# Enclosure_100x68_BHWL3.net
KiCad netlist of a schematic drawn in EAGLE
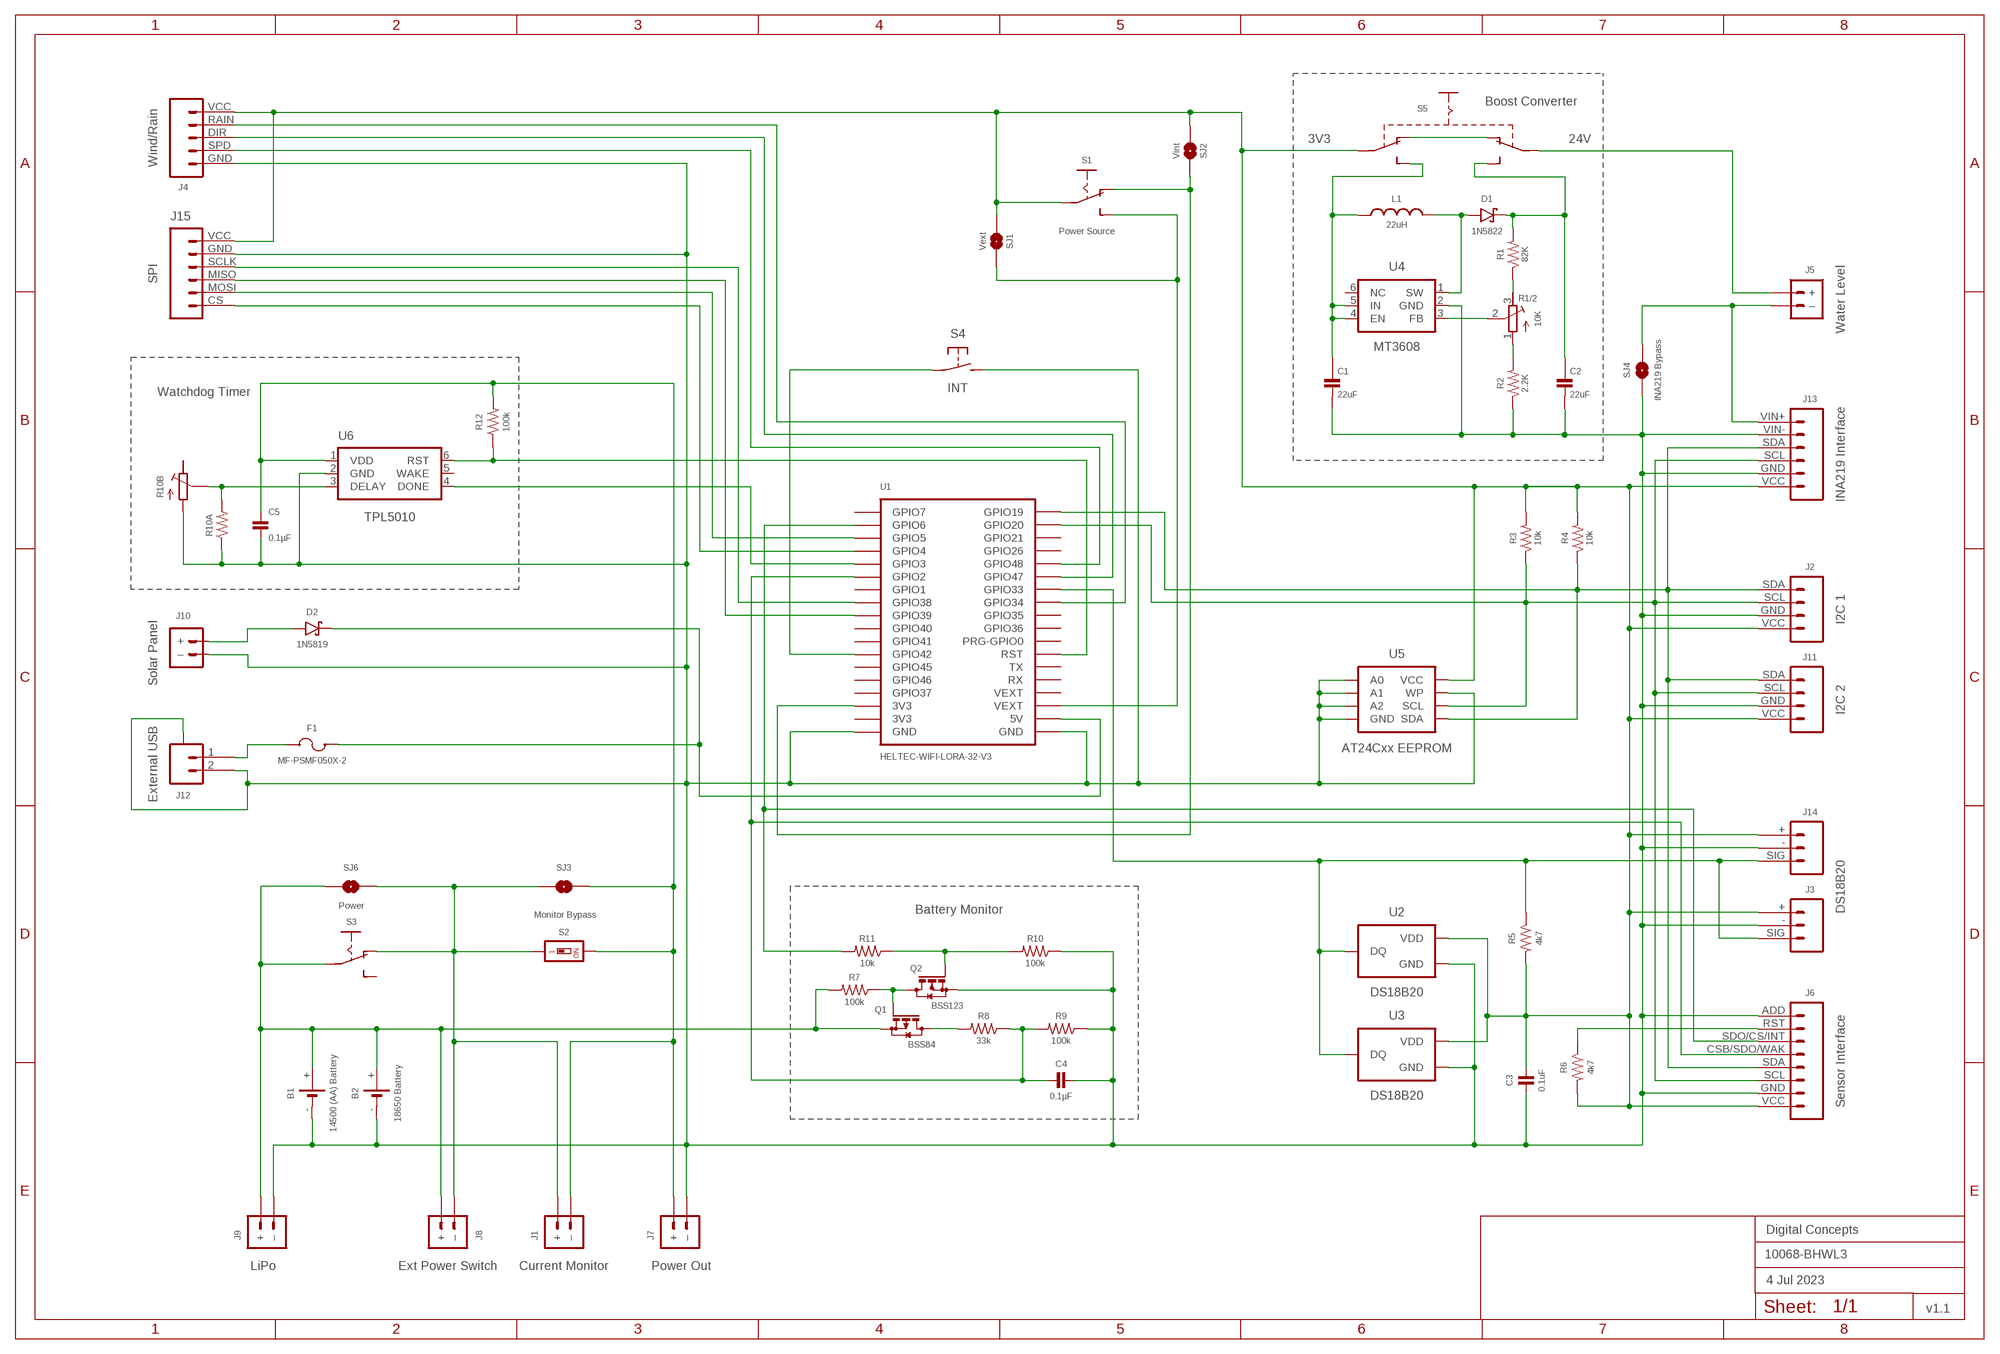
[diagram p0: schematic, sheet 1]

(export (version "E")
  (design (tool "Eeschema 10.0.6"))
  (components
    (comp (ref "B1")
      (value "14500 (AA) Battery")
      (footprint "eagle-import:BATTERY-14500")
      (libsource (lib "eagle-import") (part "BATTERY-HOLDER-14500(AA)"))
    )
    (comp (ref "B2")
      (value "18650 Battery")
      (footprint "eagle-import:BATTERY-18650")
      (libsource (lib "eagle-import") (part "BATTERY-HOLDER-18650"))
    )
    (comp (ref "C1")
      (value "22uF")
      (footprint "eagle-import:C1206")
      (libsource (lib "eagle-import") (part "CAPACITOR-1206"))
    )
    (comp (ref "C2")
      (value "22uF")
      (footprint "eagle-import:C1206")
      (libsource (lib "eagle-import") (part "CAPACITOR-1206"))
    )
    (comp (ref "C3")
      (value "0.1uF")
      (footprint "eagle-import:C0805")
      (libsource (lib "eagle-import") (part "CAPACITOR-0805"))
    )
    (comp (ref "C4")
      (value "0.1µF")
      (footprint "eagle-import:C0805")
      (libsource (lib "eagle-import") (part "CAPACITOR-0805"))
    )
    (comp (ref "C5")
      (value "0.1µF")
      (footprint "eagle-import:C0805")
      (libsource (lib "eagle-import") (part "CAPACITOR-0805"))
    )
    (comp (ref "D1")
      (value "1N5822")
      (footprint "eagle-import:DIODE_SMB")
      (libsource (lib "eagle-import") (part "DIODE-SCHOTTKY-1N5822"))
    )
    (comp (ref "D2")
      (value "1N5819")
      (footprint "eagle-import:SOD-123")
      (libsource (lib "eagle-import") (part "1N5819-SOD-123"))
    )
    (comp (ref "F1")
      (value "MF-PSMF050X-2")
      (footprint "eagle-import:F0805")
      (libsource (lib "eagle-import") (part "MF-PSMF050X-2"))
    )
    (comp (ref "J1")
      (value "Current Monitor")
      (footprint "eagle-import:JST-PH2.0-2-HORIZONTAL")
      (libsource (lib "eagle-import") (part "JST-PH2.0-2-HORIZONTALJST-PTH-2"))
    )
    (comp (ref "J2")
      (value "I2C 1")
      (footprint "eagle-import:JST-PH2.0-4-VERTICAL-I2C")
      (libsource (lib "eagle-import") (part "JST-PH2.0-4-VERTICAL-I2C"))
    )
    (comp (ref "J3")
      (value "DS18B20")
      (footprint "eagle-import:JST-PH2.0-3-VERTICAL-SIG")
      (libsource (lib "eagle-import") (part "JST-PH2.0-3-VERTICAL-DS18B20"))
    )
    (comp (ref "J4")
      (value "Wind/Rain")
      (footprint "eagle-import:JST-PH2.0-5-DUAL-WEATHER")
      (libsource (lib "eagle-import") (part "JST-PH2.0-5-DUAL-WEATHER"))
    )
    (comp (ref "J5")
      (value "Water Level")
      (footprint "eagle-import:JST-PH2.0-2-DUAL-POWER")
      (libsource (lib "eagle-import") (part "JST-PH2.0-2-DUAL-POWERJST-PTH-2"))
    )
    (comp (ref "J6")
      (value "Sensor Interface")
      (footprint "eagle-import:CONN_08-SENSOR")
      (libsource (lib "eagle-import") (part "HEADER-1X8-SENSOR"))
    )
    (comp (ref "J7")
      (value "Power Out")
      (footprint "eagle-import:JST-GH1.25-2-HORIZONTAL")
      (libsource (lib "eagle-import") (part "JST-GH1.25-2-HORIZONTAL-POWER"))
    )
    (comp (ref "J8")
      (value "Ext Power Switch")
      (footprint "eagle-import:JST-PH2.0-2-DUAL-POWER")
      (libsource (lib "eagle-import") (part "JST-PH2.0-2-DUAL-POWERJST-PTH-2"))
    )
    (comp (ref "J9")
      (value "LiPo")
      (footprint "eagle-import:JST-PH2.0-2-HORIZONTAL-POWER")
      (libsource (lib "eagle-import") (part "JST-PH2.0-2-HORIZONTAL-POWERJST-PTH-2"))
    )
    (comp (ref "J10")
      (value "Solar Panel")
      (footprint "eagle-import:JST-PH2.0-2-VERTICAL=POWER")
      (libsource (lib "eagle-import") (part "JST-PH2.0-2-VERTICAL"))
    )
    (comp (ref "J11")
      (value "I2C 2")
      (footprint "eagle-import:JST-PH2.0-4-HORIZONTAL")
      (libsource (lib "eagle-import") (part "JST-PH2.0-I2C-MALE-HORIZONTAL"))
    )
    (comp (ref "J12")
      (value "External USB")
      (footprint "eagle-import:JST-SH1.0-2-HORIZONTAL")
      (libsource (lib "eagle-import") (part "JST-SH1.0-2-SMD-HORIZONTAL"))
    )
    (comp (ref "J13")
      (value "INA219 Interface")
      (footprint "eagle-import:CONN_06-INA219")
      (libsource (lib "eagle-import") (part "INA219-I2C-MODULE"))
    )
    (comp (ref "J14")
      (value "JST-PH2.0-3-HORIZONTAL-DS18B20")
      (footprint "eagle-import:JST-PH2.0-DS18B20-HORIZONTAL")
      (libsource (lib "eagle-import") (part "JST-PH2.0-3-HORIZONTAL-DS18B20"))
    )
    (comp (ref "J15")
      (value "SPI")
      (footprint "eagle-import:JST-PH2.0-6-HORIZONTAL-SPI")
      (libsource (lib "eagle-import") (part "JST-PH2.0-6-HORIZONTAL-SPI"))
    )
    (comp (ref "L1")
      (value "22uH")
      (footprint "eagle-import:CDRH104R+6D28")
      (libsource (lib "eagle-import") (part "INDUCTOR-CDRH104R/6D28L5038P"))
    )
    (comp (ref "Q1")
      (value "BSS84")
      (footprint "eagle-import:SOT23-3")
      (libsource (lib "eagle-import") (part "BSS84"))
    )
    (comp (ref "Q2")
      (value "BSS123")
      (footprint "eagle-import:SOT23-3")
      (libsource (lib "eagle-import") (part "MOSFET-BSS123"))
    )
    (comp (ref "R1")
      (value "82K")
      (footprint "eagle-import:R0805")
      (libsource (lib "eagle-import") (part "RESISTORR0805"))
    )
    (comp (ref "R1/2")
      (value "10K")
      (footprint "eagle-import:RTRIM64P")
      (libsource (lib "eagle-import") (part "RESISTOR-TRIMM-BAOTER-HORIZONTAL"))
    )
    (comp (ref "R2")
      (value "2.2K")
      (footprint "eagle-import:R0805")
      (libsource (lib "eagle-import") (part "RESISTORR0805"))
    )
    (comp (ref "R3")
      (value "10k")
      (footprint "eagle-import:R0805")
      (libsource (lib "eagle-import") (part "RESISTORR0805"))
    )
    (comp (ref "R4")
      (value "10k")
      (footprint "eagle-import:R0805")
      (libsource (lib "eagle-import") (part "RESISTORR0805"))
    )
    (comp (ref "R5")
      (value "4k7")
      (footprint "eagle-import:R0805")
      (libsource (lib "eagle-import") (part "RESISTORR0805"))
    )
    (comp (ref "R6")
      (value "4k7")
      (footprint "eagle-import:R0805")
      (libsource (lib "eagle-import") (part "RESISTORR0805"))
    )
    (comp (ref "R7")
      (value "100k")
      (footprint "eagle-import:R0805")
      (libsource (lib "eagle-import") (part "RESISTORR0805"))
    )
    (comp (ref "R8")
      (value "33k")
      (footprint "eagle-import:R0805")
      (libsource (lib "eagle-import") (part "RESISTORR0805"))
    )
    (comp (ref "R9")
      (value "100k")
      (footprint "eagle-import:R0805")
      (libsource (lib "eagle-import") (part "RESISTORR0805"))
    )
    (comp (ref "R10")
      (value "100k")
      (footprint "eagle-import:R0805")
      (libsource (lib "eagle-import") (part "RESISTORR0805"))
    )
    (comp (ref "R10A")
      (value "RESISTORR0805")
      (footprint "eagle-import:R0805")
      (libsource (lib "eagle-import") (part "RESISTORR0805"))
    )
    (comp (ref "R10B")
      (value "RESISTOR-TRIMM-33")
      (footprint "eagle-import:RTRIM3_3")
      (libsource (lib "eagle-import") (part "RESISTOR-TRIMM-33"))
    )
    (comp (ref "R11")
      (value "10k")
      (footprint "eagle-import:R0805")
      (libsource (lib "eagle-import") (part "RESISTORR0805"))
    )
    (comp (ref "R12")
      (value "100k")
      (footprint "eagle-import:R0805")
      (libsource (lib "eagle-import") (part "RESISTORR0805"))
    )
    (comp (ref "S1")
      (value "Power Source")
      (footprint "eagle-import:SWITCH-SPDT-SMT")
      (libsource (lib "eagle-import") (part "SWITCH-SLIDE-SPDT-SMT"))
    )
    (comp (ref "S2")
      (value "Monitor Bypass")
      (footprint "eagle-import:SMD-001")
      (libsource (lib "eagle-import") (part "SWITCH-DIP-SWS001"))
    )
    (comp (ref "S3")
      (value "Power")
      (footprint "eagle-import:SWITCH-SPDT-PTH")
      (libsource (lib "eagle-import") (part "SWITCH-SLIDE-SPDT-PTH"))
    )
    (comp (ref "S4")
      (value "INT")
      (footprint "eagle-import:SWITCH-2-PAD")
      (libsource (lib "eagle-import") (part "SWITCH-MOMENTARY-2-PIN"))
    )
    (comp (ref "S5")
      (value "SWITCH-SLIDE-DPDT-PTH-S")
      (footprint "eagle-import:SWITCH-DPDT-PTH")
      (libsource (lib "eagle-import") (part "SWITCH-SLIDE-DPDT-PTH-S"))
    )
    (comp (ref "SJ1")
      (value "Vext")
      (footprint "eagle-import:SJ")
      (libsource (lib "eagle-import") (part "SJ"))
    )
    (comp (ref "SJ2")
      (value "Vint")
      (footprint "eagle-import:SJ-VIA-2")
      (libsource (lib "eagle-import") (part "SJ-V-2"))
    )
    (comp (ref "SJ3")
      (value "Monitor")
      (footprint "eagle-import:SJ")
      (libsource (lib "eagle-import") (part "SJ"))
    )
    (comp (ref "SJ4")
      (value "INA219 Bypass")
      (footprint "eagle-import:SJ")
      (libsource (lib "eagle-import") (part "SJ"))
    )
    (comp (ref "SJ6")
      (value "Power")
      (footprint "eagle-import:SJ")
      (libsource (lib "eagle-import") (part "SJ"))
    )
    (comp (ref "U1")
      (value "HELTEC-WIFI-LORA-32-V3")
      (footprint "eagle-import:HELTEC-WIFI-LORA-32-V3")
      (libsource (lib "eagle-import") (part "HELTEC-WIFI-LORA-32-V3"))
    )
    (comp (ref "U2")
      (value "DS18B20")
      (footprint "eagle-import:TO-92")
      (fields (field (name "MF") "Maxim Integrated"))
      (libsource (lib "eagle-import") (part "THERMOMETER-DS18B20"))
    )
    (comp (ref "U3")
      (value "DS18B20")
      (footprint "eagle-import:TO-92")
      (fields (field (name "MF") "Maxim Integrated"))
      (libsource (lib "eagle-import") (part "THERMOMETER-DS18B20"))
    )
    (comp (ref "U4")
      (value "MT3608")
      (footprint "eagle-import:SOT-23-6@1")
      (libsource (lib "eagle-import") (part "MT3608"))
    )
    (comp (ref "U5")
      (value "AT24Cxx EEPROM")
      (footprint "eagle-import:SOP-8")
      (libsource (lib "eagle-import") (part "AT24CXX-EEPROM"))
    )
    (comp (ref "U6")
      (value "TPL5010")
      (footprint "eagle-import:SOT-23-6")
      (libsource (lib "eagle-import") (part "TPL5010DDCR"))
    )
  )
  (nets
    (net (code "1") (name "Net-(D2-PadA)") (class "Default")
      (node (ref "D2") (pin "A") (pinfunction "A_A") (pintype "passive"))
      (node (ref "J10") (pin "+") (pinfunction "+_+") (pintype "power_in"))
    )
    (net (code "2") (name "Net-(D2-PadC)") (class "Default")
      (node (ref "D2") (pin "C") (pinfunction "C_C") (pintype "passive"))
      (node (ref "F1") (pin "1") (pinfunction "1_1") (pintype "passive"))
      (node (ref "U1") (pin "5V") (pinfunction "5V_5V") (pintype "bidirectional"))
    )
    (net (code "3") (name "Net-(F1-Pad2)") (class "Default")
      (node (ref "F1") (pin "2") (pinfunction "2_2") (pintype "passive"))
      (node (ref "J12") (pin "1") (pinfunction "1_1") (pintype "passive"))
    )
    (net (code "4") (name "Net-(J1-+)") (class "Default")
      (node (ref "J1") (pin "1") (pinfunction "+_1") (pintype "power_in"))
      (node (ref "J8") (pin "-") (pinfunction "–_-") (pintype "power_in"))
      (node (ref "S2") (pin "1") (pinfunction "1_1") (pintype "passive"))
      (node (ref "S3") (pin "1") (pinfunction "O_1") (pintype "passive"))
      (node (ref "SJ3") (pin "2") (pinfunction "2_2") (pintype "passive"))
      (node (ref "SJ6") (pin "1") (pinfunction "1_1") (pintype "passive"))
    )
    (net (code "5") (name "Net-(J1-–)") (class "Default")
      (node (ref "C5") (pin "1") (pinfunction "1_1") (pintype "passive"))
      (node (ref "J1") (pin "2") (pinfunction "–_2") (pintype "power_in"))
      (node (ref "J7") (pin "+") (pinfunction "+_+") (pintype "power_in"))
      (node (ref "R12") (pin "2") (pinfunction "2_2") (pintype "passive"))
      (node (ref "S2") (pin "2") (pinfunction "2_2") (pintype "passive"))
      (node (ref "SJ3") (pin "1") (pinfunction "1_1") (pintype "passive"))
      (node (ref "U6") (pin "1") (pinfunction "VDD_1") (pintype "power_in"))
    )
    (net (code "6") (name "Net-(J4-2)") (class "Default")
      (node (ref "J4") (pin "RAIN") (pinfunction "2_RAIN") (pintype "passive"))
      (node (ref "U1") (pin "GPIO34") (pinfunction "GPIO34_GPIO34") (pintype "bidirectional"))
    )
    (net (code "7") (name "Net-(J4-3)") (class "Default")
      (node (ref "J4") (pin "DIR") (pinfunction "3_DIR") (pintype "passive"))
      (node (ref "U1") (pin "GPIO47") (pinfunction "GPIO47_GPIO47") (pintype "bidirectional"))
    )
    (net (code "8") (name "Net-(J4-4)") (class "Default")
      (node (ref "J4") (pin "SPD") (pinfunction "4_SPD") (pintype "passive"))
      (node (ref "U1") (pin "GPIO48") (pinfunction "GPIO48_GPIO48") (pintype "bidirectional"))
    )
    (net (code "9") (name "Net-(J6-5)") (class "Default")
      (node (ref "C4") (pin "1") (pinfunction "1_1") (pintype "passive"))
      (node (ref "J6") (pin "CSB/SDO/WAK") (pinfunction "5_CSB/SDO/WAK") (pintype "passive"))
      (node (ref "R8") (pin "1") (pinfunction "1_1") (pintype "passive"))
      (node (ref "R9") (pin "2") (pinfunction "2_2") (pintype "passive"))
      (node (ref "U1") (pin "GPIO2") (pinfunction "GPIO2_GPIO2") (pintype "bidirectional"))
    )
    (net (code "10") (name "Net-(J6-6)") (class "Default")
      (node (ref "J6") (pin "SDO/CS/INT") (pinfunction "6_SDO/CS/INT") (pintype "passive"))
      (node (ref "R11") (pin "2") (pinfunction "2_2") (pintype "passive"))
      (node (ref "U1") (pin "GPIO6") (pinfunction "GPIO6_GPIO6") (pintype "bidirectional"))
    )
    (net (code "11") (name "Net-(J6-7)") (class "Default")
      (node (ref "J6") (pin "RST") (pinfunction "7_RST") (pintype "passive"))
      (node (ref "R6") (pin "1") (pinfunction "1_1") (pintype "passive"))
    )
    (net (code "12") (name "Net-(J10-–)") (class "Default")
      (node (ref "B1") (pin "-") (pinfunction "-_-") (pintype "power_in"))
      (node (ref "B2") (pin "-") (pinfunction "-_-") (pintype "power_in"))
      (node (ref "C1") (pin "2") (pinfunction "2_2") (pintype "passive"))
      (node (ref "C2") (pin "2") (pinfunction "2_2") (pintype "passive"))
      (node (ref "C3") (pin "2") (pinfunction "2_2") (pintype "passive"))
      (node (ref "C4") (pin "2") (pinfunction "2_2") (pintype "passive"))
      (node (ref "C5") (pin "2") (pinfunction "2_2") (pintype "passive"))
      (node (ref "J10") (pin "-") (pinfunction "–_-") (pintype "power_in"))
      (node (ref "J11") (pin "GND") (pinfunction "2_GND") (pintype "passive"))
      (node (ref "J12") (pin "2") (pinfunction "2_2") (pintype "passive"))
      (node (ref "J12") (pin "A@1") (pinfunction "A_A@1") (pintype "power_in"))
      (node (ref "J12") (pin "A@2") (pinfunction "A_A@2") (pintype "power_in"))
      (node (ref "J13") (pin "GND") (pinfunction "2_GND") (pintype "passive"))
      (node (ref "J13") (pin "VIN-") (pinfunction "5_VIN-") (pintype "passive"))
      (node (ref "J14") (pin "-") (pinfunction "2_-") (pintype "passive"))
      (node (ref "J15") (pin "GND") (pinfunction "5_GND") (pintype "passive"))
      (node (ref "J2") (pin "GND") (pinfunction "3_GND") (pintype "passive"))
      (node (ref "J3") (pin "-") (pinfunction "2_-") (pintype "passive"))
      (node (ref "J4") (pin "GND") (pinfunction "5_GND") (pintype "passive"))
      (node (ref "J6") (pin "ADD") (pinfunction "8_ADD") (pintype "passive"))
      (node (ref "J6") (pin "GND") (pinfunction "2_GND") (pintype "passive"))
      (node (ref "J7") (pin "-") (pinfunction "–_-") (pintype "power_in"))
      (node (ref "J9") (pin "-") (pinfunction "–_-") (pintype "power_in"))
      (node (ref "Q2") (pin "2") (pinfunction "S_2") (pintype "passive"))
      (node (ref "R10") (pin "1") (pinfunction "1_1") (pintype "passive"))
      (node (ref "R10A") (pin "1") (pinfunction "1_1") (pintype "passive"))
      (node (ref "R10B") (pin "1") (pinfunction "A_1") (pintype "passive"))
      (node (ref "R2") (pin "1") (pinfunction "1_1") (pintype "passive"))
      (node (ref "R9") (pin "1") (pinfunction "1_1") (pintype "passive"))
      (node (ref "S4") (pin "P$2") (pinfunction "S_P$2") (pintype "passive"))
      (node (ref "SJ4") (pin "1") (pinfunction "1_1") (pintype "passive"))
      (node (ref "U1") (pin "GND@1") (pinfunction "GND_GND@1") (pintype "bidirectional"))
      (node (ref "U1") (pin "GND@36") (pinfunction "GND_GND@36") (pintype "bidirectional"))
      (node (ref "U2") (pin "1") (pinfunction "GND_1") (pintype "power_in"))
      (node (ref "U3") (pin "1") (pinfunction "GND_1") (pintype "power_in"))
      (node (ref "U4") (pin "2") (pinfunction "GND_2") (pintype "power_in"))
      (node (ref "U5") (pin "P$1") (pinfunction "A0_P$1") (pintype "bidirectional"))
      (node (ref "U5") (pin "P$2") (pinfunction "A1_P$2") (pintype "bidirectional"))
      (node (ref "U5") (pin "P$3") (pinfunction "A2_P$3") (pintype "bidirectional"))
      (node (ref "U5") (pin "P$4") (pinfunction "GND_P$4") (pintype "bidirectional"))
      (node (ref "U5") (pin "P$7") (pinfunction "WP_P$7") (pintype "bidirectional"))
      (node (ref "U6") (pin "2") (pinfunction "GND_2") (pintype "power_in"))
    )
    (net (code "13") (name "Net-(J11-1)") (class "Default")
      (node (ref "C3") (pin "1") (pinfunction "1_1") (pintype "passive"))
      (node (ref "J11") (pin "VCC") (pinfunction "1_VCC") (pintype "passive"))
      (node (ref "J13") (pin "VCC") (pinfunction "1_VCC") (pintype "passive"))
      (node (ref "J14") (pin "+") (pinfunction "3_+") (pintype "passive"))
      (node (ref "J15") (pin "VCC") (pinfunction "6_VCC") (pintype "passive"))
      (node (ref "J2") (pin "VCC") (pinfunction "4_VCC") (pintype "passive"))
      (node (ref "J3") (pin "+") (pinfunction "3_+") (pintype "passive"))
      (node (ref "J4") (pin "VCC") (pinfunction "1_VCC") (pintype "passive"))
      (node (ref "J6") (pin "VCC") (pinfunction "1_VCC") (pintype "passive"))
      (node (ref "R3") (pin "2") (pinfunction "2_2") (pintype "passive"))
      (node (ref "R4") (pin "2") (pinfunction "2_2") (pintype "passive"))
      (node (ref "R5") (pin "2") (pinfunction "2_2") (pintype "passive"))
      (node (ref "R6") (pin "2") (pinfunction "2_2") (pintype "passive"))
      (node (ref "S1") (pin "2") (pinfunction "P_2") (pintype "passive"))
      (node (ref "S5") (pin "P$5") (pinfunction "P2_P$5") (pintype "passive"))
      (node (ref "SJ1") (pin "2") (pinfunction "2_2") (pintype "passive"))
      (node (ref "SJ2") (pin "2") (pinfunction "2_2") (pintype "passive"))
      (node (ref "SJ2") (pin "2@V") (pinfunction "2_2@V") (pintype "passive"))
      (node (ref "U2") (pin "3") (pinfunction "VDD_3") (pintype "power_in"))
      (node (ref "U3") (pin "3") (pinfunction "VDD_3") (pintype "power_in"))
      (node (ref "U5") (pin "P$8") (pinfunction "VCC_P$8") (pintype "bidirectional"))
    )
    (net (code "14") (name "Net-(J11-3)") (class "Default")
      (node (ref "J11") (pin "SCL") (pinfunction "3_SCL") (pintype "passive"))
      (node (ref "J13") (pin "SCL") (pinfunction "3_SCL") (pintype "passive"))
      (node (ref "J2") (pin "SCL") (pinfunction "2_SCL") (pintype "passive"))
      (node (ref "J6") (pin "SCL") (pinfunction "3_SCL") (pintype "passive"))
      (node (ref "R3") (pin "1") (pinfunction "1_1") (pintype "passive"))
      (node (ref "U1") (pin "GPIO20") (pinfunction "GPIO20_GPIO20") (pintype "bidirectional"))
      (node (ref "U5") (pin "P$6") (pinfunction "SCL_P$6") (pintype "bidirectional"))
    )
    (net (code "15") (name "Net-(J11-4)") (class "Default")
      (node (ref "J11") (pin "SDA") (pinfunction "4_SDA") (pintype "passive"))
      (node (ref "J13") (pin "SDA") (pinfunction "4_SDA") (pintype "passive"))
      (node (ref "J2") (pin "SDA") (pinfunction "1_SDA") (pintype "passive"))
      (node (ref "J6") (pin "SDA") (pinfunction "4_SDA") (pintype "passive"))
      (node (ref "R4") (pin "1") (pinfunction "1_1") (pintype "passive"))
      (node (ref "U1") (pin "GPIO19") (pinfunction "GPIO19_GPIO19") (pintype "bidirectional"))
      (node (ref "U5") (pin "P$5") (pinfunction "SDA_P$5") (pintype "bidirectional"))
    )
    (net (code "16") (name "Net-(J13-6)") (class "Default")
      (node (ref "J13") (pin "VIN+") (pinfunction "6_VIN+") (pintype "passive"))
      (node (ref "J5") (pin "-") (pinfunction "–_-") (pintype "power_in"))
      (node (ref "SJ4") (pin "2") (pinfunction "2_2") (pintype "passive"))
    )
    (net (code "17") (name "Net-(J14-1)") (class "Default")
      (node (ref "J14") (pin "SIG") (pinfunction "1_SIG") (pintype "passive"))
      (node (ref "J3") (pin "SIG") (pinfunction "1_SIG") (pintype "passive"))
      (node (ref "R5") (pin "1") (pinfunction "1_1") (pintype "passive"))
      (node (ref "U1") (pin "GPIO33") (pinfunction "GPIO33_GPIO33") (pintype "bidirectional"))
      (node (ref "U2") (pin "2") (pinfunction "DQ_2") (pintype "bidirectional"))
      (node (ref "U3") (pin "2") (pinfunction "DQ_2") (pintype "bidirectional"))
    )
    (net (code "18") (name "Net-(J15-1)") (class "Default")
      (node (ref "J15") (pin "CS") (pinfunction "1_CS") (pintype "passive"))
      (node (ref "U1") (pin "GPIO4") (pinfunction "GPIO4_GPIO4") (pintype "bidirectional"))
    )
    (net (code "19") (name "Net-(J15-2)") (class "Default")
      (node (ref "J15") (pin "MOSI") (pinfunction "2_MOSI") (pintype "passive"))
      (node (ref "U1") (pin "GPIO5") (pinfunction "GPIO5_GPIO5") (pintype "bidirectional"))
    )
    (net (code "20") (name "Net-(J15-3)") (class "Default")
      (node (ref "J15") (pin "MISO") (pinfunction "3_MISO") (pintype "passive"))
      (node (ref "U1") (pin "GPIO39") (pinfunction "GPIO39_GPIO39") (pintype "bidirectional"))
    )
    (net (code "21") (name "Net-(J15-4)") (class "Default")
      (node (ref "J15") (pin "SCLK") (pinfunction "4_SCLK") (pintype "passive"))
      (node (ref "U1") (pin "GPIO38") (pinfunction "GPIO38_GPIO38") (pintype "bidirectional"))
    )
    (net (code "22") (name "Net-(Q1-D)") (class "Default")
      (node (ref "Q1") (pin "3") (pinfunction "D_3") (pintype "passive"))
      (node (ref "R8") (pin "2") (pinfunction "2_2") (pintype "passive"))
    )
    (net (code "23") (name "Net-(Q1-G)") (class "Default")
      (node (ref "Q1") (pin "1") (pinfunction "G_1") (pintype "passive"))
      (node (ref "Q2") (pin "3") (pinfunction "D_3") (pintype "passive"))
      (node (ref "R7") (pin "1") (pinfunction "1_1") (pintype "passive"))
    )
    (net (code "24") (name "Net-(Q1-S)") (class "Default")
      (node (ref "B1") (pin "+") (pinfunction "+_+") (pintype "power_in"))
      (node (ref "B2") (pin "+") (pinfunction "+_+") (pintype "power_in"))
      (node (ref "J8") (pin "+") (pinfunction "+_+") (pintype "power_in"))
      (node (ref "J9") (pin "+") (pinfunction "+_+") (pintype "power_in"))
      (node (ref "Q1") (pin "2") (pinfunction "S_2") (pintype "passive"))
      (node (ref "R7") (pin "2") (pinfunction "2_2") (pintype "passive"))
      (node (ref "S3") (pin "2") (pinfunction "P_2") (pintype "passive"))
      (node (ref "SJ6") (pin "2") (pinfunction "2_2") (pintype "passive"))
    )
    (net (code "25") (name "Net-(Q2-G)") (class "Default")
      (node (ref "Q2") (pin "1") (pinfunction "G_1") (pintype "passive"))
      (node (ref "R10") (pin "2") (pinfunction "2_2") (pintype "passive"))
      (node (ref "R11") (pin "1") (pinfunction "1_1") (pintype "passive"))
    )
    (net (code "26") (name "Net-(R1/2-A)") (class "Default")
      (node (ref "R1/2") (pin "1") (pinfunction "A_1") (pintype "passive"))
      (node (ref "R2") (pin "2") (pinfunction "2_2") (pintype "passive"))
    )
    (net (code "27") (name "Net-(R1/2-E)") (class "Default")
      (node (ref "R1") (pin "1") (pinfunction "1_1") (pintype "passive"))
      (node (ref "R1/2") (pin "3") (pinfunction "E_3") (pintype "passive"))
    )
    (net (code "28") (name "Net-(R1/2-S)") (class "Default")
      (node (ref "R1/2") (pin "2") (pinfunction "S_2") (pintype "passive"))
      (node (ref "U4") (pin "3") (pinfunction "FB_3") (pintype "input"))
    )
    (net (code "29") (name "Net-(R10B-S)") (class "Default")
      (node (ref "R10A") (pin "2") (pinfunction "2_2") (pintype "passive"))
      (node (ref "R10B") (pin "2") (pinfunction "S_2") (pintype "passive"))
      (node (ref "U6") (pin "3") (pinfunction "DELAY_3") (pintype "input"))
    )
    (net (code "30") (name "Net-(S1-O)") (class "Default")
      (node (ref "S1") (pin "1") (pinfunction "O_1") (pintype "passive"))
      (node (ref "SJ2") (pin "1") (pinfunction "1_1") (pintype "passive"))
      (node (ref "U1") (pin "3V3@34") (pinfunction "3V3_3V3@34") (pintype "bidirectional"))
    )
    (net (code "31") (name "Net-(S1-S)") (class "Default")
      (node (ref "S1") (pin "3") (pinfunction "S_3") (pintype "passive"))
      (node (ref "SJ1") (pin "1") (pinfunction "1_1") (pintype "passive"))
      (node (ref "U1") (pin "VEXT@3") (pinfunction "VEXT_VEXT@3") (pintype "bidirectional"))
    )
    (net (code "32") (name "Net-(S4-P)") (class "Default")
      (node (ref "S4") (pin "P$1") (pinfunction "P_P$1") (pintype "passive"))
      (node (ref "U1") (pin "GPIO42") (pinfunction "GPIO42_GPIO42") (pintype "bidirectional"))
    )
    (net (code "33") (name "Net-(S5-O1)") (class "Default")
      (node (ref "S5") (pin "P$1") (pinfunction "O1_P$1") (pintype "passive"))
      (node (ref "S5") (pin "P$4") (pinfunction "O2_P$4") (pintype "passive"))
    )
    (net (code "34") (name "Net-(S5-P1)") (class "Default")
      (node (ref "J5") (pin "+") (pinfunction "+_+") (pintype "power_in"))
      (node (ref "S5") (pin "P$2") (pinfunction "P1_P$2") (pintype "passive"))
    )
    (net (code "35") (name "Net-(S5-S1)") (class "Default")
      (node (ref "C2") (pin "1") (pinfunction "1_1") (pintype "passive"))
      (node (ref "D1") (pin "C") (pinfunction "C_C") (pintype "passive"))
      (node (ref "R1") (pin "2") (pinfunction "2_2") (pintype "passive"))
      (node (ref "S5") (pin "P$3") (pinfunction "S1_P$3") (pintype "passive"))
    )
    (net (code "36") (name "Net-(S5-S2)") (class "Default")
      (node (ref "C1") (pin "1") (pinfunction "1_1") (pintype "passive"))
      (node (ref "L1") (pin "2") (pinfunction "2_2") (pintype "passive"))
      (node (ref "S5") (pin "P$6") (pinfunction "S2_P$6") (pintype "passive"))
      (node (ref "U4") (pin "4") (pinfunction "EN_4") (pintype "input"))
      (node (ref "U4") (pin "5") (pinfunction "IN_5") (pintype "power_in"))
    )
    (net (code "37") (name "Net-(U4-SW)") (class "Default")
      (node (ref "D1") (pin "A") (pinfunction "A_A") (pintype "passive"))
      (node (ref "L1") (pin "1") (pinfunction "1_1") (pintype "passive"))
      (node (ref "U4") (pin "1") (pinfunction "SW_1") (pintype "power_in"))
    )
    (net (code "38") (name "Net-(U6-DONE)") (class "Default")
      (node (ref "U1") (pin "GPIO3") (pinfunction "GPIO3_GPIO3") (pintype "bidirectional"))
      (node (ref "U6") (pin "4") (pinfunction "DONE_4") (pintype "input"))
    )
    (net (code "39") (name "Net-(U6-RST)") (class "Default")
      (node (ref "R12") (pin "1") (pinfunction "1_1") (pintype "passive"))
      (node (ref "U1") (pin "RST") (pinfunction "RST_RST") (pintype "bidirectional"))
      (node (ref "U6") (pin "6") (pinfunction "RST_6") (pintype "output"))
    )
    (net (code "40") (name "unconnected-(R10B-E-Pad3)") (class "Default")
      (node (ref "R10B") (pin "3") (pinfunction "E_3") (pintype "passive"))
    )
    (net (code "41") (name "unconnected-(S3-S-Pad3)") (class "Default")
      (node (ref "S3") (pin "3") (pinfunction "S_3") (pintype "passive"))
    )
    (net (code "42") (name "unconnected-(U1-3V3-Pad3V3@35)") (class "Default")
      (node (ref "U1") (pin "3V3@35") (pinfunction "3V3_3V3@35") (pintype "bidirectional"))
    )
    (net (code "43") (name "unconnected-(U1-PRG-GPIO0-PadGPIO0)") (class "Default")
      (node (ref "U1") (pin "GPIO0") (pinfunction "PRG-GPIO0_GPIO0") (pintype "bidirectional"))
    )
    (net (code "44") (name "unconnected-(U1-PadGPIO1)") (class "Default")
      (node (ref "U1") (pin "GPIO1") (pinfunction "GPIO1_GPIO1") (pintype "bidirectional"))
    )
    (net (code "45") (name "unconnected-(U1-PadGPIO7)") (class "Default")
      (node (ref "U1") (pin "GPIO7") (pinfunction "GPIO7_GPIO7") (pintype "bidirectional"))
    )
    (net (code "46") (name "unconnected-(U1-PadGPIO21)") (class "Default")
      (node (ref "U1") (pin "GPIO21") (pinfunction "GPIO21_GPIO21") (pintype "bidirectional"))
    )
    (net (code "47") (name "unconnected-(U1-PadGPIO26)") (class "Default")
      (node (ref "U1") (pin "GPIO26") (pinfunction "GPIO26_GPIO26") (pintype "bidirectional"))
    )
    (net (code "48") (name "unconnected-(U1-PadGPIO35)") (class "Default")
      (node (ref "U1") (pin "GPIO35") (pinfunction "GPIO35_GPIO35") (pintype "bidirectional"))
    )
    (net (code "49") (name "unconnected-(U1-PadGPIO36)") (class "Default")
      (node (ref "U1") (pin "GPIO36") (pinfunction "GPIO36_GPIO36") (pintype "bidirectional"))
    )
    (net (code "50") (name "unconnected-(U1-PadGPIO37)") (class "Default")
      (node (ref "U1") (pin "GPIO37") (pinfunction "GPIO37_GPIO37") (pintype "bidirectional"))
    )
    (net (code "51") (name "unconnected-(U1-PadGPIO40)") (class "Default")
      (node (ref "U1") (pin "GPIO40") (pinfunction "GPIO40_GPIO40") (pintype "bidirectional"))
    )
    (net (code "52") (name "unconnected-(U1-PadGPIO41)") (class "Default")
      (node (ref "U1") (pin "GPIO41") (pinfunction "GPIO41_GPIO41") (pintype "bidirectional"))
    )
    (net (code "53") (name "unconnected-(U1-PadGPIO45)") (class "Default")
      (node (ref "U1") (pin "GPIO45") (pinfunction "GPIO45_GPIO45") (pintype "bidirectional"))
    )
    (net (code "54") (name "unconnected-(U1-PadGPIO46)") (class "Default")
      (node (ref "U1") (pin "GPIO46") (pinfunction "GPIO46_GPIO46") (pintype "bidirectional"))
    )
    (net (code "55") (name "unconnected-(U1-PadRX)") (class "Default")
      (node (ref "U1") (pin "RX") (pinfunction "RX_RX") (pintype "bidirectional"))
    )
    (net (code "56") (name "unconnected-(U1-PadTX)") (class "Default")
      (node (ref "U1") (pin "TX") (pinfunction "TX_TX") (pintype "bidirectional"))
    )
    (net (code "57") (name "unconnected-(U1-VEXT-PadVEXT@4)") (class "Default")
      (node (ref "U1") (pin "VEXT@4") (pinfunction "VEXT_VEXT@4") (pintype "bidirectional"))
    )
    (net (code "58") (name "unconnected-(U4-NC-Pad6)") (class "Default")
      (node (ref "U4") (pin "6") (pinfunction "NC_6") (pintype "no_connect"))
    )
    (net (code "59") (name "unconnected-(U6-WAKE-Pad5)") (class "Default")
      (node (ref "U6") (pin "5") (pinfunction "WAKE_5") (pintype "output"))
    )
  )
)
